# Sheet1.net
KiCad netlist of a schematic drawn in Altium Designer
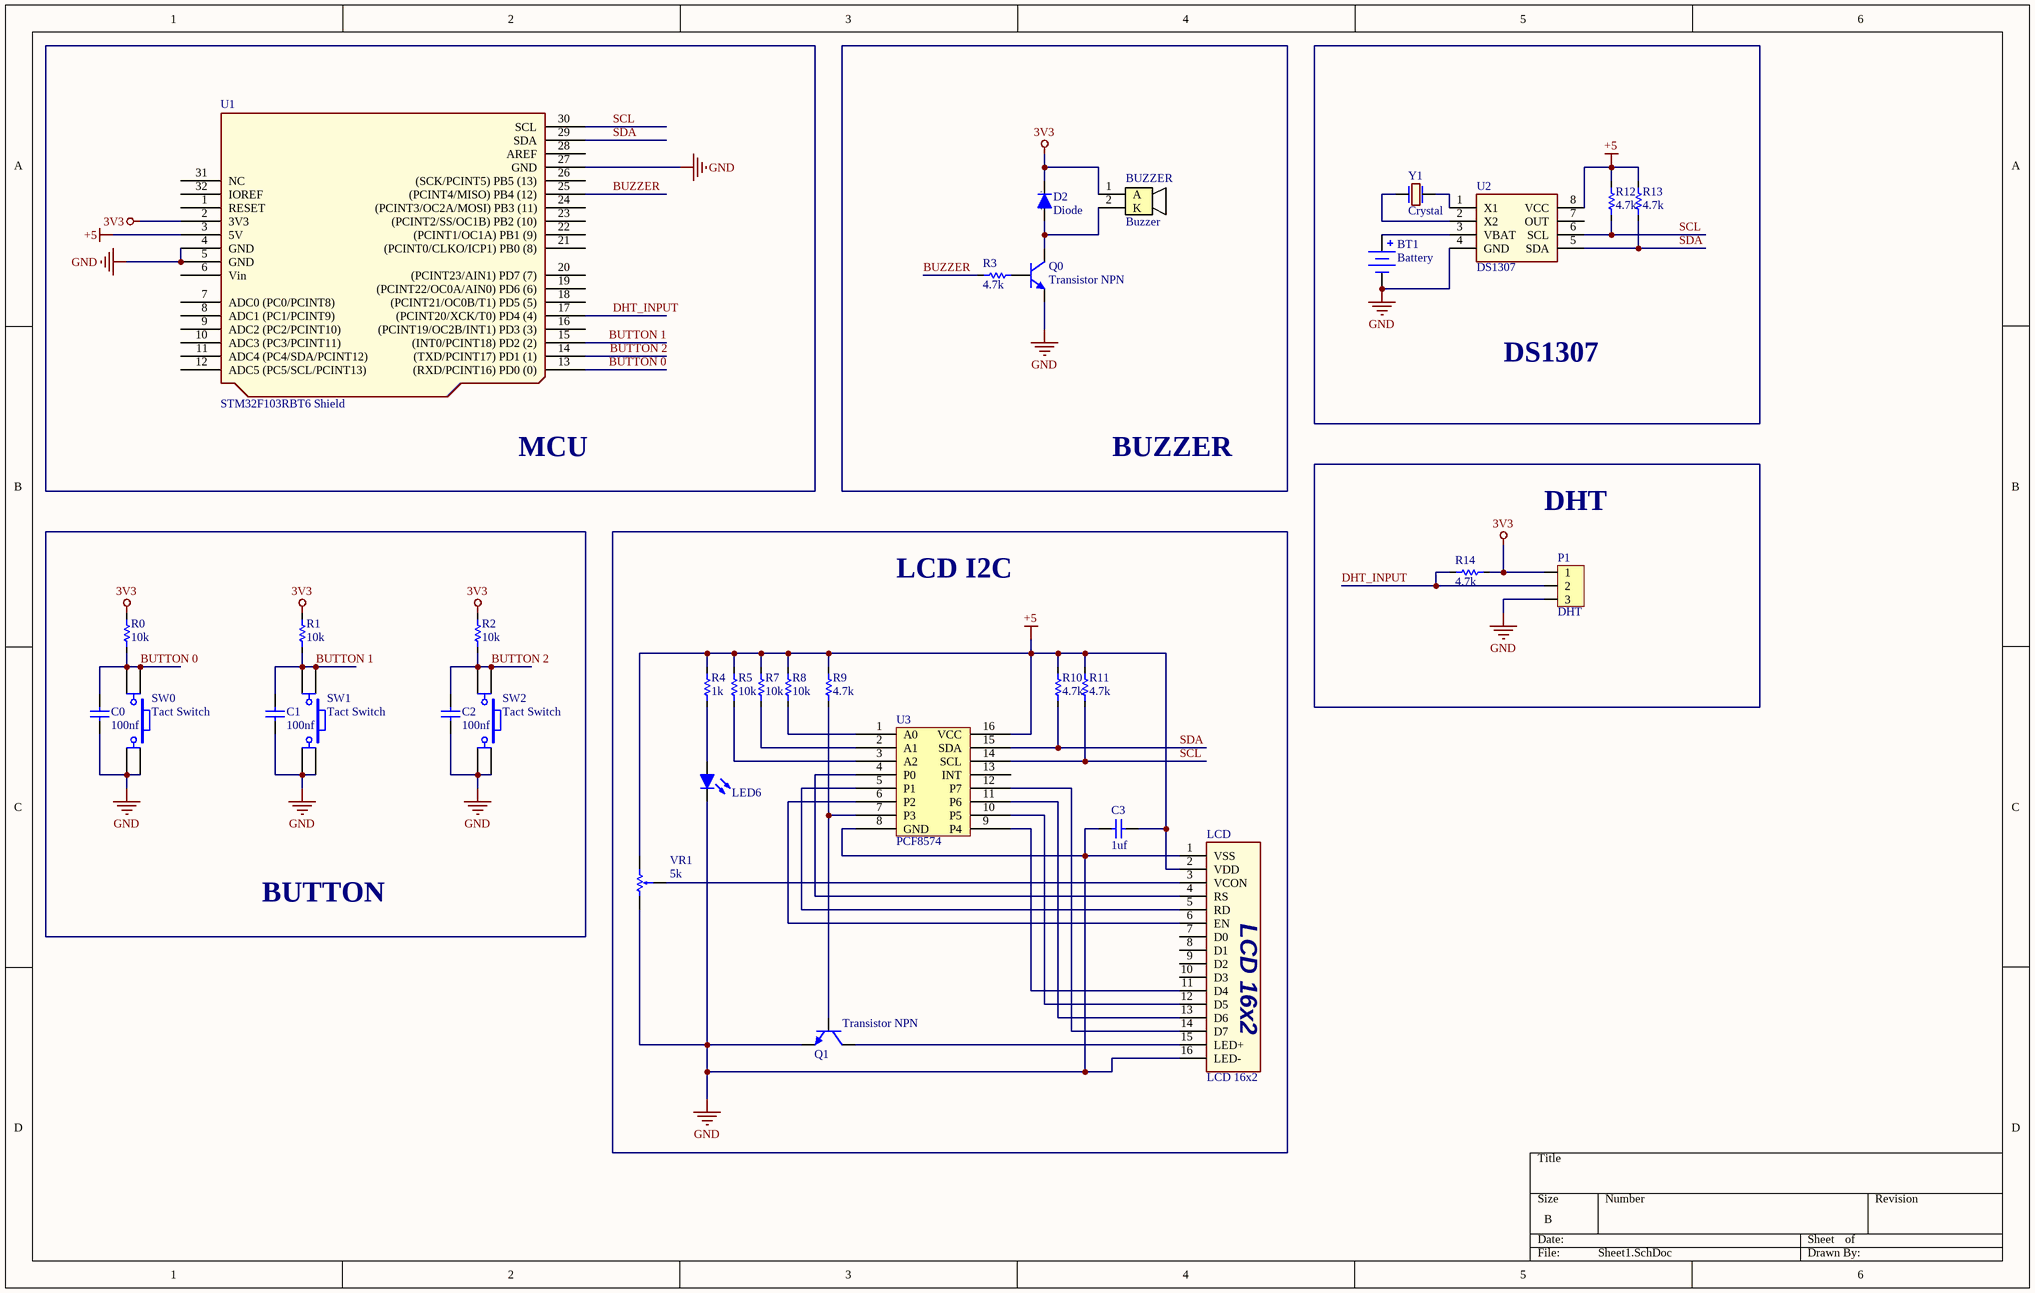
[diagram p0: Sheet1.SchDoc]

(export (version "E")
  (design (tool "Eeschema 10.0.6"))
  (components
    (comp (ref "BT1")
      (value "Battery")
      (footprint "CON CR2032")
      (libsource (lib "BKIT4U_LIB_NEW") (part "Battery"))
    )
    (comp (ref "BUZZER")
      (value "Buzzer")
      (footprint "BUZZER")
      (libsource (lib "BKIT4U_LIB_NEW") (part "Buzzer"))
    )
    (comp (ref "C0")
      (value "100nf")
      (footprint "C 0805 (2012)")
      (description "Capacitor non-pol")
      (libsource (lib "BKIT4U_LIB_NEW") (part "Capacitor NP"))
    )
    (comp (ref "C1")
      (value "100nf")
      (footprint "C 0805 (2012)")
      (description "Capacitor non-pol")
      (libsource (lib "BKIT4U_LIB_NEW") (part "Capacitor NP"))
    )
    (comp (ref "C2")
      (value "100nf")
      (footprint "C 0805 (2012)")
      (description "Capacitor non-pol")
      (libsource (lib "BKIT4U_LIB_NEW") (part "Capacitor NP"))
    )
    (comp (ref "C3")
      (value "1uf")
      (footprint "C 0805 (2012)")
      (description "Capacitor non-pol")
      (libsource (lib "BKIT4U_LIB_NEW") (part "Capacitor NP"))
    )
    (comp (ref "D2")
      (value "Diode")
      (footprint "SOD-80")
      (description "Default Diode")
      (fields (field (name "PUBLISHER") "Altium Limited"))
      (libsource (lib "BKIT4U_LIB_NEW") (part "Diode"))
    )
    (comp (ref "LCD")
      (value "LCD 16x2")
      (footprint "BKIT4U_LIB_NEW:LCD 16x2")
      (description "Character LCD 16x2")
      (libsource (lib "BKIT4U_LIB_NEW") (part "LCD 16x2"))
    )
    (comp (ref "LED6")
      (value "Led")
      (footprint "Led SMD 0805")
      (description "Typical LED")
      (libsource (lib "BKIT4U_LIB_NEW") (part "Led"))
    )
    (comp (ref "P1")
      (value "DHT")
      (footprint "XH2.54-3P")
      (description "Header, 3-Pin")
      (libsource (lib "BKIT4U_LIB_NEW") (part "Header 3"))
    )
    (comp (ref "Q0")
      (value "Transistor NPN")
      (footprint "SOT-23")
      (description "NPN Bipolar Transistor")
      (libsource (lib "BKIT4U_LIB_NEW") (part "Transistor NPN"))
    )
    (comp (ref "Q1")
      (value "Transistor NPN")
      (footprint "SOT-23")
      (description "NPN Bipolar Transistor")
      (libsource (lib "BKIT4U_LIB_NEW") (part "Transistor NPN"))
    )
    (comp (ref "R0")
      (value "10k")
      (footprint "R 0805 (2012)")
      (description "Resistor")
      (fields (field (name "PUBLISHER") "Altium Limited"))
      (libsource (lib "BKIT4U_LIB_NEW") (part "Resistor"))
    )
    (comp (ref "R1")
      (value "10k")
      (footprint "R 0805 (2012)")
      (description "Resistor")
      (fields (field (name "PUBLISHER") "Altium Limited"))
      (libsource (lib "BKIT4U_LIB_NEW") (part "Resistor"))
    )
    (comp (ref "R2")
      (value "10k")
      (footprint "R 0805 (2012)")
      (description "Resistor")
      (fields (field (name "PUBLISHER") "Altium Limited"))
      (libsource (lib "BKIT4U_LIB_NEW") (part "Resistor"))
    )
    (comp (ref "R3")
      (value "4.7k")
      (footprint "R 0805 (2012)")
      (description "Resistor")
      (fields (field (name "PUBLISHER") "Altium Limited"))
      (libsource (lib "BKIT4U_LIB_NEW") (part "Resistor"))
    )
    (comp (ref "R4")
      (value "1k")
      (footprint "R 0805 (2012)")
      (description "Resistor")
      (fields (field (name "PUBLISHER") "Altium Limited"))
      (libsource (lib "BKIT4U_LIB_NEW") (part "Resistor"))
    )
    (comp (ref "R5")
      (value "10k")
      (footprint "R 0805 (2012)")
      (description "Resistor")
      (fields (field (name "PUBLISHER") "Altium Limited"))
      (libsource (lib "BKIT4U_LIB_NEW") (part "Resistor"))
    )
    (comp (ref "R7")
      (value "10k")
      (footprint "R 0805 (2012)")
      (description "Resistor")
      (fields (field (name "PUBLISHER") "Altium Limited"))
      (libsource (lib "BKIT4U_LIB_NEW") (part "Resistor"))
    )
    (comp (ref "R8")
      (value "10k")
      (footprint "R 0805 (2012)")
      (description "Resistor")
      (fields (field (name "PUBLISHER") "Altium Limited"))
      (libsource (lib "BKIT4U_LIB_NEW") (part "Resistor"))
    )
    (comp (ref "R9")
      (value "4.7k")
      (footprint "R 0805 (2012)")
      (description "Resistor")
      (fields (field (name "PUBLISHER") "Altium Limited"))
      (libsource (lib "BKIT4U_LIB_NEW") (part "Resistor"))
    )
    (comp (ref "R10")
      (value "4.7k")
      (footprint "R 0805 (2012)")
      (description "Resistor")
      (fields (field (name "PUBLISHER") "Altium Limited"))
      (libsource (lib "BKIT4U_LIB_NEW") (part "Resistor"))
    )
    (comp (ref "R11")
      (value "4.7k")
      (footprint "R 0805 (2012)")
      (description "Resistor")
      (fields (field (name "PUBLISHER") "Altium Limited"))
      (libsource (lib "BKIT4U_LIB_NEW") (part "Resistor"))
    )
    (comp (ref "R12")
      (value "4.7k")
      (footprint "R 0805 (2012)")
      (description "Resistor")
      (fields (field (name "PUBLISHER") "Altium Limited"))
      (libsource (lib "BKIT4U_LIB_NEW") (part "Resistor"))
    )
    (comp (ref "R13")
      (value "4.7k")
      (footprint "R 0805 (2012)")
      (description "Resistor")
      (fields (field (name "PUBLISHER") "Altium Limited"))
      (libsource (lib "BKIT4U_LIB_NEW") (part "Resistor"))
    )
    (comp (ref "R14")
      (value "4.7k")
      (footprint "R 0805 (2012)")
      (description "Resistor")
      (fields (field (name "PUBLISHER") "Altium Limited"))
      (libsource (lib "BKIT4U_LIB_NEW") (part "Resistor"))
    )
    (comp (ref "SW0")
      (value "Tact Switch")
      (footprint "SW/4/DIP 12x12x7")
      (description "Tact switch 4 pin")
      (libsource (lib "BKIT4U_LIB_NEW") (part "SW SPST-4"))
    )
    (comp (ref "SW1")
      (value "Tact Switch")
      (footprint "SW/4/DIP 12x12x7")
      (description "Tact switch 4 pin")
      (libsource (lib "BKIT4U_LIB_NEW") (part "SW SPST-4"))
    )
    (comp (ref "SW2")
      (value "Tact Switch")
      (footprint "SW/4/DIP 12x12x7")
      (description "Tact switch 4 pin")
      (libsource (lib "BKIT4U_LIB_NEW") (part "SW SPST-4"))
    )
    (comp (ref "U1")
      (value "STM32F103RBT6 Shield")
      (footprint "Arduino Uno R3 Shield 2xPins")
      (description "Arduino Uno R3 shield pins connection")
      (libsource (lib "BKIT4U_LIB_NEW") (part "Arduino Uno R3 shield"))
    )
    (comp (ref "U2") (value "DS1307") (footprint "DIP 8") (libsource (lib "BKIT4U_LIB_NEW") (part "DS1307")))
    (comp (ref "U3")
      (value "PCF8574")
      (footprint "SnapEDApcb:SOIC127P1032X265-16N")
      (description "Remote 8-Bit I/O Expander for I  2C Bus")
      (libsource (lib "Custom Library") (part "PCF8574"))
    )
    (comp (ref "VR1")
      (value "5k")
      (footprint "R Var 3mm")
      (description "Resistor Variable")
      (libsource (lib "chipfc_libs") (part "Resistor Variable"))
    )
    (comp (ref "Y1")
      (value "Crystal")
      (footprint "Crystal DIP-2")
      (libsource (lib "BKIT4U_LIB_NEW") (part "Crystal"))
    )
  )
  (nets
    (net (code "1") (name "+5") (class "Default")
      (node (ref "C3") (pin "2") (pinfunction "2_2") (pintype "passive"))
      (node (ref "LCD") (pin "2") (pinfunction "VDD_2") (pintype "passive"))
      (node (ref "R10") (pin "2") (pinfunction "2_2") (pintype "passive"))
      (node (ref "R11") (pin "2") (pinfunction "2_2") (pintype "passive"))
      (node (ref "R12") (pin "2") (pinfunction "2_2") (pintype "passive"))
      (node (ref "R13") (pin "2") (pinfunction "2_2") (pintype "passive"))
      (node (ref "R4") (pin "2") (pinfunction "2_2") (pintype "passive"))
      (node (ref "R5") (pin "2") (pinfunction "2_2") (pintype "passive"))
      (node (ref "R7") (pin "2") (pinfunction "2_2") (pintype "passive"))
      (node (ref "R8") (pin "2") (pinfunction "2_2") (pintype "passive"))
      (node (ref "R9") (pin "2") (pinfunction "2_2") (pintype "passive"))
      (node (ref "U1") (pin "3") (pinfunction "5V_3") (pintype "passive"))
      (node (ref "U2") (pin "8") (pinfunction "VCC_8") (pintype "passive"))
      (node (ref "U3") (pin "16") (pinfunction "VCC_16") (pintype "passive"))
      (node (ref "VR1") (pin "1") (pinfunction "1_1") (pintype "passive"))
    )
    (net (code "2") (name "/BUTTON 0") (class "Default")
      (node (ref "C0") (pin "1") (pinfunction "1_1") (pintype "passive"))
      (node (ref "R0") (pin "1") (pinfunction "1_1") (pintype "passive"))
      (node (ref "SW0") (pin "1") (pinfunction "1_1") (pintype "passive"))
      (node (ref "SW0") (pin "4") (pinfunction "2_4") (pintype "passive"))
      (node (ref "U1") (pin "13") (pinfunction "(RXD/PCINT16)_PD0_(0)_13") (pintype "passive"))
    )
    (net (code "3") (name "/BUTTON 1") (class "Default")
      (node (ref "C1") (pin "1") (pinfunction "1_1") (pintype "passive"))
      (node (ref "R1") (pin "1") (pinfunction "1_1") (pintype "passive"))
      (node (ref "SW1") (pin "1") (pinfunction "1_1") (pintype "passive"))
      (node (ref "SW1") (pin "4") (pinfunction "2_4") (pintype "passive"))
      (node (ref "U1") (pin "15") (pinfunction "(INT0/PCINT18)_PD2_(2)_15") (pintype "passive"))
    )
    (net (code "4") (name "/BUTTON 2") (class "Default")
      (node (ref "C2") (pin "1") (pinfunction "1_1") (pintype "passive"))
      (node (ref "R2") (pin "1") (pinfunction "1_1") (pintype "passive"))
      (node (ref "SW2") (pin "1") (pinfunction "1_1") (pintype "passive"))
      (node (ref "SW2") (pin "4") (pinfunction "2_4") (pintype "passive"))
      (node (ref "U1") (pin "14") (pinfunction "(TXD/PCINT17)_PD1_(1)_14") (pintype "passive"))
    )
    (net (code "5") (name "/BUZZER") (class "Default")
      (node (ref "R3") (pin "1") (pinfunction "1_1") (pintype "passive"))
      (node (ref "U1") (pin "25") (pinfunction "(PCINT4/MISO)_PB4_(12)_25") (pintype "passive"))
    )
    (net (code "6") (name "/DHT_INPUT") (class "Default")
      (node (ref "P1") (pin "2") (pinfunction "2_2") (pintype "passive"))
      (node (ref "R14") (pin "2") (pinfunction "2_2") (pintype "passive"))
      (node (ref "U1") (pin "17") (pinfunction "(PCINT20/XCK/T0)_PD4_(4)_17") (pintype "passive"))
    )
    (net (code "7") (name "/SCL") (class "Default")
      (node (ref "R11") (pin "1") (pinfunction "1_1") (pintype "passive"))
      (node (ref "R12") (pin "1") (pinfunction "1_1") (pintype "passive"))
      (node (ref "U1") (pin "30") (pinfunction "SCL_30") (pintype "passive"))
      (node (ref "U2") (pin "6") (pinfunction "SCL_6") (pintype "passive"))
      (node (ref "U3") (pin "14") (pinfunction "SCL_14") (pintype "passive"))
    )
    (net (code "8") (name "/SDA") (class "Default")
      (node (ref "R10") (pin "1") (pinfunction "1_1") (pintype "passive"))
      (node (ref "R13") (pin "1") (pinfunction "1_1") (pintype "passive"))
      (node (ref "U1") (pin "29") (pinfunction "SDA_29") (pintype "passive"))
      (node (ref "U2") (pin "5") (pinfunction "SDA_5") (pintype "passive"))
      (node (ref "U3") (pin "15") (pinfunction "SDA_15") (pintype "passive"))
    )
    (net (code "9") (name "3V3") (class "Default")
      (node (ref "BUZZER") (pin "1") (pinfunction "A_1") (pintype "passive"))
      (node (ref "D2") (pin "1") (pinfunction "Cathode_1") (pintype "passive"))
      (node (ref "P1") (pin "1") (pinfunction "1_1") (pintype "passive"))
      (node (ref "R0") (pin "2") (pinfunction "2_2") (pintype "passive"))
      (node (ref "R1") (pin "2") (pinfunction "2_2") (pintype "passive"))
      (node (ref "R14") (pin "1") (pinfunction "1_1") (pintype "passive"))
      (node (ref "R2") (pin "2") (pinfunction "2_2") (pintype "passive"))
      (node (ref "U1") (pin "2") (pinfunction "3V3_2") (pintype "passive"))
    )
    (net (code "10") (name "GND") (class "Default")
      (node (ref "BT1") (pin "2") (pinfunction "GND_2") (pintype "passive"))
      (node (ref "C0") (pin "2") (pinfunction "2_2") (pintype "passive"))
      (node (ref "C1") (pin "2") (pinfunction "2_2") (pintype "passive"))
      (node (ref "C2") (pin "2") (pinfunction "2_2") (pintype "passive"))
      (node (ref "C3") (pin "1") (pinfunction "1_1") (pintype "passive"))
      (node (ref "LCD") (pin "1") (pinfunction "VSS_1") (pintype "passive"))
      (node (ref "LCD") (pin "16") (pinfunction "LED-_16") (pintype "passive"))
      (node (ref "LED6") (pin "1") (pinfunction "K_1") (pintype "passive"))
      (node (ref "P1") (pin "3") (pinfunction "3_3") (pintype "passive"))
      (node (ref "Q0") (pin "2") (pinfunction "E_2") (pintype "passive"))
      (node (ref "Q1") (pin "2") (pinfunction "E_2") (pintype "passive"))
      (node (ref "SW0") (pin "2") (pinfunction "2_2") (pintype "passive"))
      (node (ref "SW0") (pin "3") (pinfunction "1_3") (pintype "passive"))
      (node (ref "SW1") (pin "2") (pinfunction "2_2") (pintype "passive"))
      (node (ref "SW1") (pin "3") (pinfunction "1_3") (pintype "passive"))
      (node (ref "SW2") (pin "2") (pinfunction "2_2") (pintype "passive"))
      (node (ref "SW2") (pin "3") (pinfunction "1_3") (pintype "passive"))
      (node (ref "U1") (pin "27") (pinfunction "GND_27") (pintype "power_in"))
      (node (ref "U1") (pin "4") (pinfunction "GND_4") (pintype "power_in"))
      (node (ref "U1") (pin "5") (pinfunction "GND_5") (pintype "power_in"))
      (node (ref "U2") (pin "4") (pinfunction "GND_4") (pintype "passive"))
      (node (ref "U3") (pin "8") (pinfunction "GND_8") (pintype "passive"))
      (node (ref "VR1") (pin "3") (pinfunction "3_3") (pintype "passive"))
    )
    (net (code "11") (name "Net-(BT1-VCC)") (class "Default")
      (node (ref "BT1") (pin "1") (pinfunction "VCC_1") (pintype "passive"))
      (node (ref "U2") (pin "3") (pinfunction "VBAT_3") (pintype "passive"))
    )
    (net (code "12") (name "Net-(BUZZER-K)") (class "Default")
      (node (ref "BUZZER") (pin "2") (pinfunction "K_2") (pintype "passive"))
      (node (ref "D2") (pin "2") (pinfunction "Anode_2") (pintype "passive"))
      (node (ref "Q0") (pin "3") (pinfunction "C_3") (pintype "passive"))
    )
    (net (code "13") (name "Net-(LCD-D4)") (class "Default")
      (node (ref "LCD") (pin "11") (pinfunction "D4_11") (pintype "passive"))
      (node (ref "U3") (pin "9") (pinfunction "P4_9") (pintype "passive"))
    )
    (net (code "14") (name "Net-(LCD-D5)") (class "Default")
      (node (ref "LCD") (pin "12") (pinfunction "D5_12") (pintype "passive"))
      (node (ref "U3") (pin "10") (pinfunction "P5_10") (pintype "passive"))
    )
    (net (code "15") (name "Net-(LCD-D6)") (class "Default")
      (node (ref "LCD") (pin "13") (pinfunction "D6_13") (pintype "passive"))
      (node (ref "U3") (pin "11") (pinfunction "P6_11") (pintype "passive"))
    )
    (net (code "16") (name "Net-(LCD-D7)") (class "Default")
      (node (ref "LCD") (pin "14") (pinfunction "D7_14") (pintype "passive"))
      (node (ref "U3") (pin "12") (pinfunction "P7_12") (pintype "passive"))
    )
    (net (code "17") (name "Net-(LCD-EN)") (class "Default")
      (node (ref "LCD") (pin "6") (pinfunction "EN_6") (pintype "passive"))
      (node (ref "U3") (pin "6") (pinfunction "P2_6") (pintype "passive"))
    )
    (net (code "18") (name "Net-(LCD-LED+)") (class "Default")
      (node (ref "LCD") (pin "15") (pinfunction "LED+_15") (pintype "passive"))
      (node (ref "Q1") (pin "3") (pinfunction "C_3") (pintype "passive"))
    )
    (net (code "19") (name "Net-(LCD-RD)") (class "Default")
      (node (ref "LCD") (pin "5") (pinfunction "RD_5") (pintype "passive"))
      (node (ref "U3") (pin "5") (pinfunction "P1_5") (pintype "passive"))
    )
    (net (code "20") (name "Net-(LCD-RS)") (class "Default")
      (node (ref "LCD") (pin "4") (pinfunction "RS_4") (pintype "passive"))
      (node (ref "U3") (pin "4") (pinfunction "P0_4") (pintype "passive"))
    )
    (net (code "21") (name "Net-(LCD-VCON)") (class "Default")
      (node (ref "LCD") (pin "3") (pinfunction "VCON_3") (pintype "passive"))
      (node (ref "VR1") (pin "2") (pinfunction "2_2") (pintype "passive"))
    )
    (net (code "22") (name "Net-(LED6-A)") (class "Default")
      (node (ref "LED6") (pin "2") (pinfunction "A_2") (pintype "passive"))
      (node (ref "R4") (pin "1") (pinfunction "1_1") (pintype "passive"))
    )
    (net (code "23") (name "Net-(Q0-B)") (class "Default")
      (node (ref "Q0") (pin "1") (pinfunction "B_1") (pintype "passive"))
      (node (ref "R3") (pin "2") (pinfunction "2_2") (pintype "passive"))
    )
    (net (code "24") (name "Net-(Q1-B)") (class "Default")
      (node (ref "Q1") (pin "1") (pinfunction "B_1") (pintype "passive"))
      (node (ref "R9") (pin "1") (pinfunction "1_1") (pintype "passive"))
      (node (ref "U3") (pin "7") (pinfunction "P3_7") (pintype "passive"))
    )
    (net (code "25") (name "Net-(U2-X1)") (class "Default")
      (node (ref "U2") (pin "1") (pinfunction "X1_1") (pintype "passive"))
      (node (ref "Y1") (pin "2") (pinfunction "2_2") (pintype "passive"))
    )
    (net (code "26") (name "Net-(U2-X2)") (class "Default")
      (node (ref "U2") (pin "2") (pinfunction "X2_2") (pintype "passive"))
      (node (ref "Y1") (pin "1") (pinfunction "1_1") (pintype "passive"))
    )
    (net (code "27") (name "Net-(U3-A0)") (class "Default")
      (node (ref "R8") (pin "1") (pinfunction "1_1") (pintype "passive"))
      (node (ref "U3") (pin "1") (pinfunction "A0_1") (pintype "passive"))
    )
    (net (code "28") (name "Net-(U3-A1)") (class "Default")
      (node (ref "R7") (pin "1") (pinfunction "1_1") (pintype "passive"))
      (node (ref "U3") (pin "2") (pinfunction "A1_2") (pintype "passive"))
    )
    (net (code "29") (name "Net-(U3-A2)") (class "Default")
      (node (ref "R5") (pin "1") (pinfunction "1_1") (pintype "passive"))
      (node (ref "U3") (pin "3") (pinfunction "A2_3") (pintype "passive"))
    )
    (net (code "30") (name "unconnected-(LCD-D0-Pad7)") (class "Default")
      (node (ref "LCD") (pin "7") (pinfunction "D0_7") (pintype "passive"))
    )
    (net (code "31") (name "unconnected-(LCD-D1-Pad8)") (class "Default")
      (node (ref "LCD") (pin "8") (pinfunction "D1_8") (pintype "passive"))
    )
    (net (code "32") (name "unconnected-(LCD-D2-Pad9)") (class "Default")
      (node (ref "LCD") (pin "9") (pinfunction "D2_9") (pintype "passive"))
    )
    (net (code "33") (name "unconnected-(LCD-D3-Pad10)") (class "Default")
      (node (ref "LCD") (pin "10") (pinfunction "D3_10") (pintype "passive"))
    )
    (net (code "34") (name "unconnected-(U1-(PCINT0{slash}CLKO{slash}ICP1)_PB0_(8)-Pad21)") (class "Default")
      (node (ref "U1") (pin "21") (pinfunction "(PCINT0/CLKO/ICP1)_PB0_(8)_21") (pintype "passive"))
    )
    (net (code "35") (name "unconnected-(U1-(PCINT1{slash}OC1A)_PB1_(9)-Pad22)") (class "Default")
      (node (ref "U1") (pin "22") (pinfunction "(PCINT1/OC1A)_PB1_(9)_22") (pintype "passive"))
    )
    (net (code "36") (name "unconnected-(U1-(PCINT2{slash}SS{slash}OC1B)_PB2_(10)-Pad23)") (class "Default")
      (node (ref "U1") (pin "23") (pinfunction "(PCINT2/SS/OC1B)_PB2_(10)_23") (pintype "passive"))
    )
    (net (code "37") (name "unconnected-(U1-(PCINT3{slash}OC2A{slash}MOSI)_PB3_(11)-Pad24)") (class "Default")
      (node (ref "U1") (pin "24") (pinfunction "(PCINT3/OC2A/MOSI)_PB3_(11)_24") (pintype "passive"))
    )
    (net (code "38") (name "unconnected-(U1-(PCINT19{slash}OC2B{slash}INT1)_PD3_(3)-Pad16)") (class "Default")
      (node (ref "U1") (pin "16") (pinfunction "(PCINT19/OC2B/INT1)_PD3_(3)_16") (pintype "passive"))
    )
    (net (code "39") (name "unconnected-(U1-(PCINT21{slash}OC0B{slash}T1)_PD5_(5)-Pad18)") (class "Default")
      (node (ref "U1") (pin "18") (pinfunction "(PCINT21/OC0B/T1)_PD5_(5)_18") (pintype "passive"))
    )
    (net (code "40") (name "unconnected-(U1-(PCINT22{slash}OC0A{slash}AIN0)_PD6_(6)-Pad19)") (class "Default")
      (node (ref "U1") (pin "19") (pinfunction "(PCINT22/OC0A/AIN0)_PD6_(6)_19") (pintype "passive"))
    )
    (net (code "41") (name "unconnected-(U1-(PCINT23{slash}AIN1)_PD7_(7)-Pad20)") (class "Default")
      (node (ref "U1") (pin "20") (pinfunction "(PCINT23/AIN1)_PD7_(7)_20") (pintype "passive"))
    )
    (net (code "42") (name "unconnected-(U1-(SCK{slash}PCINT5)_PB5_(13)-Pad26)") (class "Default")
      (node (ref "U1") (pin "26") (pinfunction "(SCK/PCINT5)_PB5_(13)_26") (pintype "passive"))
    )
    (net (code "43") (name "unconnected-(U1-ADC0_(PC0{slash}PCINT8)-Pad7)") (class "Default")
      (node (ref "U1") (pin "7") (pinfunction "ADC0_(PC0/PCINT8)_7") (pintype "passive"))
    )
    (net (code "44") (name "unconnected-(U1-ADC1_(PC1{slash}PCINT9)-Pad8)") (class "Default")
      (node (ref "U1") (pin "8") (pinfunction "ADC1_(PC1/PCINT9)_8") (pintype "passive"))
    )
    (net (code "45") (name "unconnected-(U1-ADC2_(PC2{slash}PCINT10)-Pad9)") (class "Default")
      (node (ref "U1") (pin "9") (pinfunction "ADC2_(PC2/PCINT10)_9") (pintype "passive"))
    )
    (net (code "46") (name "unconnected-(U1-ADC3_(PC3{slash}PCINT11)-Pad10)") (class "Default")
      (node (ref "U1") (pin "10") (pinfunction "ADC3_(PC3/PCINT11)_10") (pintype "passive"))
    )
    (net (code "47") (name "unconnected-(U1-ADC4_(PC4{slash}SDA{slash}PCINT12)-Pad11)") (class "Default")
      (node (ref "U1") (pin "11") (pinfunction "ADC4_(PC4/SDA/PCINT12)_11") (pintype "passive"))
    )
    (net (code "48") (name "unconnected-(U1-ADC5_(PC5{slash}SCL{slash}PCINT13)-Pad12)") (class "Default")
      (node (ref "U1") (pin "12") (pinfunction "ADC5_(PC5/SCL/PCINT13)_12") (pintype "passive"))
    )
    (net (code "49") (name "unconnected-(U1-AREF-Pad28)") (class "Default")
      (node (ref "U1") (pin "28") (pinfunction "AREF_28") (pintype "passive"))
    )
    (net (code "50") (name "unconnected-(U1-IOREF-Pad32)") (class "Default")
      (node (ref "U1") (pin "32") (pinfunction "IOREF_32") (pintype "passive"))
    )
    (net (code "51") (name "unconnected-(U1-NC-Pad31)") (class "Default")
      (node (ref "U1") (pin "31") (pinfunction "NC_31") (pintype "passive"))
    )
    (net (code "52") (name "unconnected-(U1-RESET-Pad1)") (class "Default")
      (node (ref "U1") (pin "1") (pinfunction "RESET_1") (pintype "passive"))
    )
    (net (code "53") (name "unconnected-(U1-Vin-Pad6)") (class "Default")
      (node (ref "U1") (pin "6") (pinfunction "Vin_6") (pintype "passive"))
    )
    (net (code "54") (name "unconnected-(U2-OUT-Pad7)") (class "Default")
      (node (ref "U2") (pin "7") (pinfunction "OUT_7") (pintype "passive"))
    )
    (net (code "55") (name "unconnected-(U3-INT-Pad13)") (class "Default")
      (node (ref "U3") (pin "13") (pinfunction "INT_13") (pintype "passive"))
    )
  )
)
